# doodle_with_onboard_clock_smd_7805.net
KiCad netlist of a schematic drawn in EAGLE
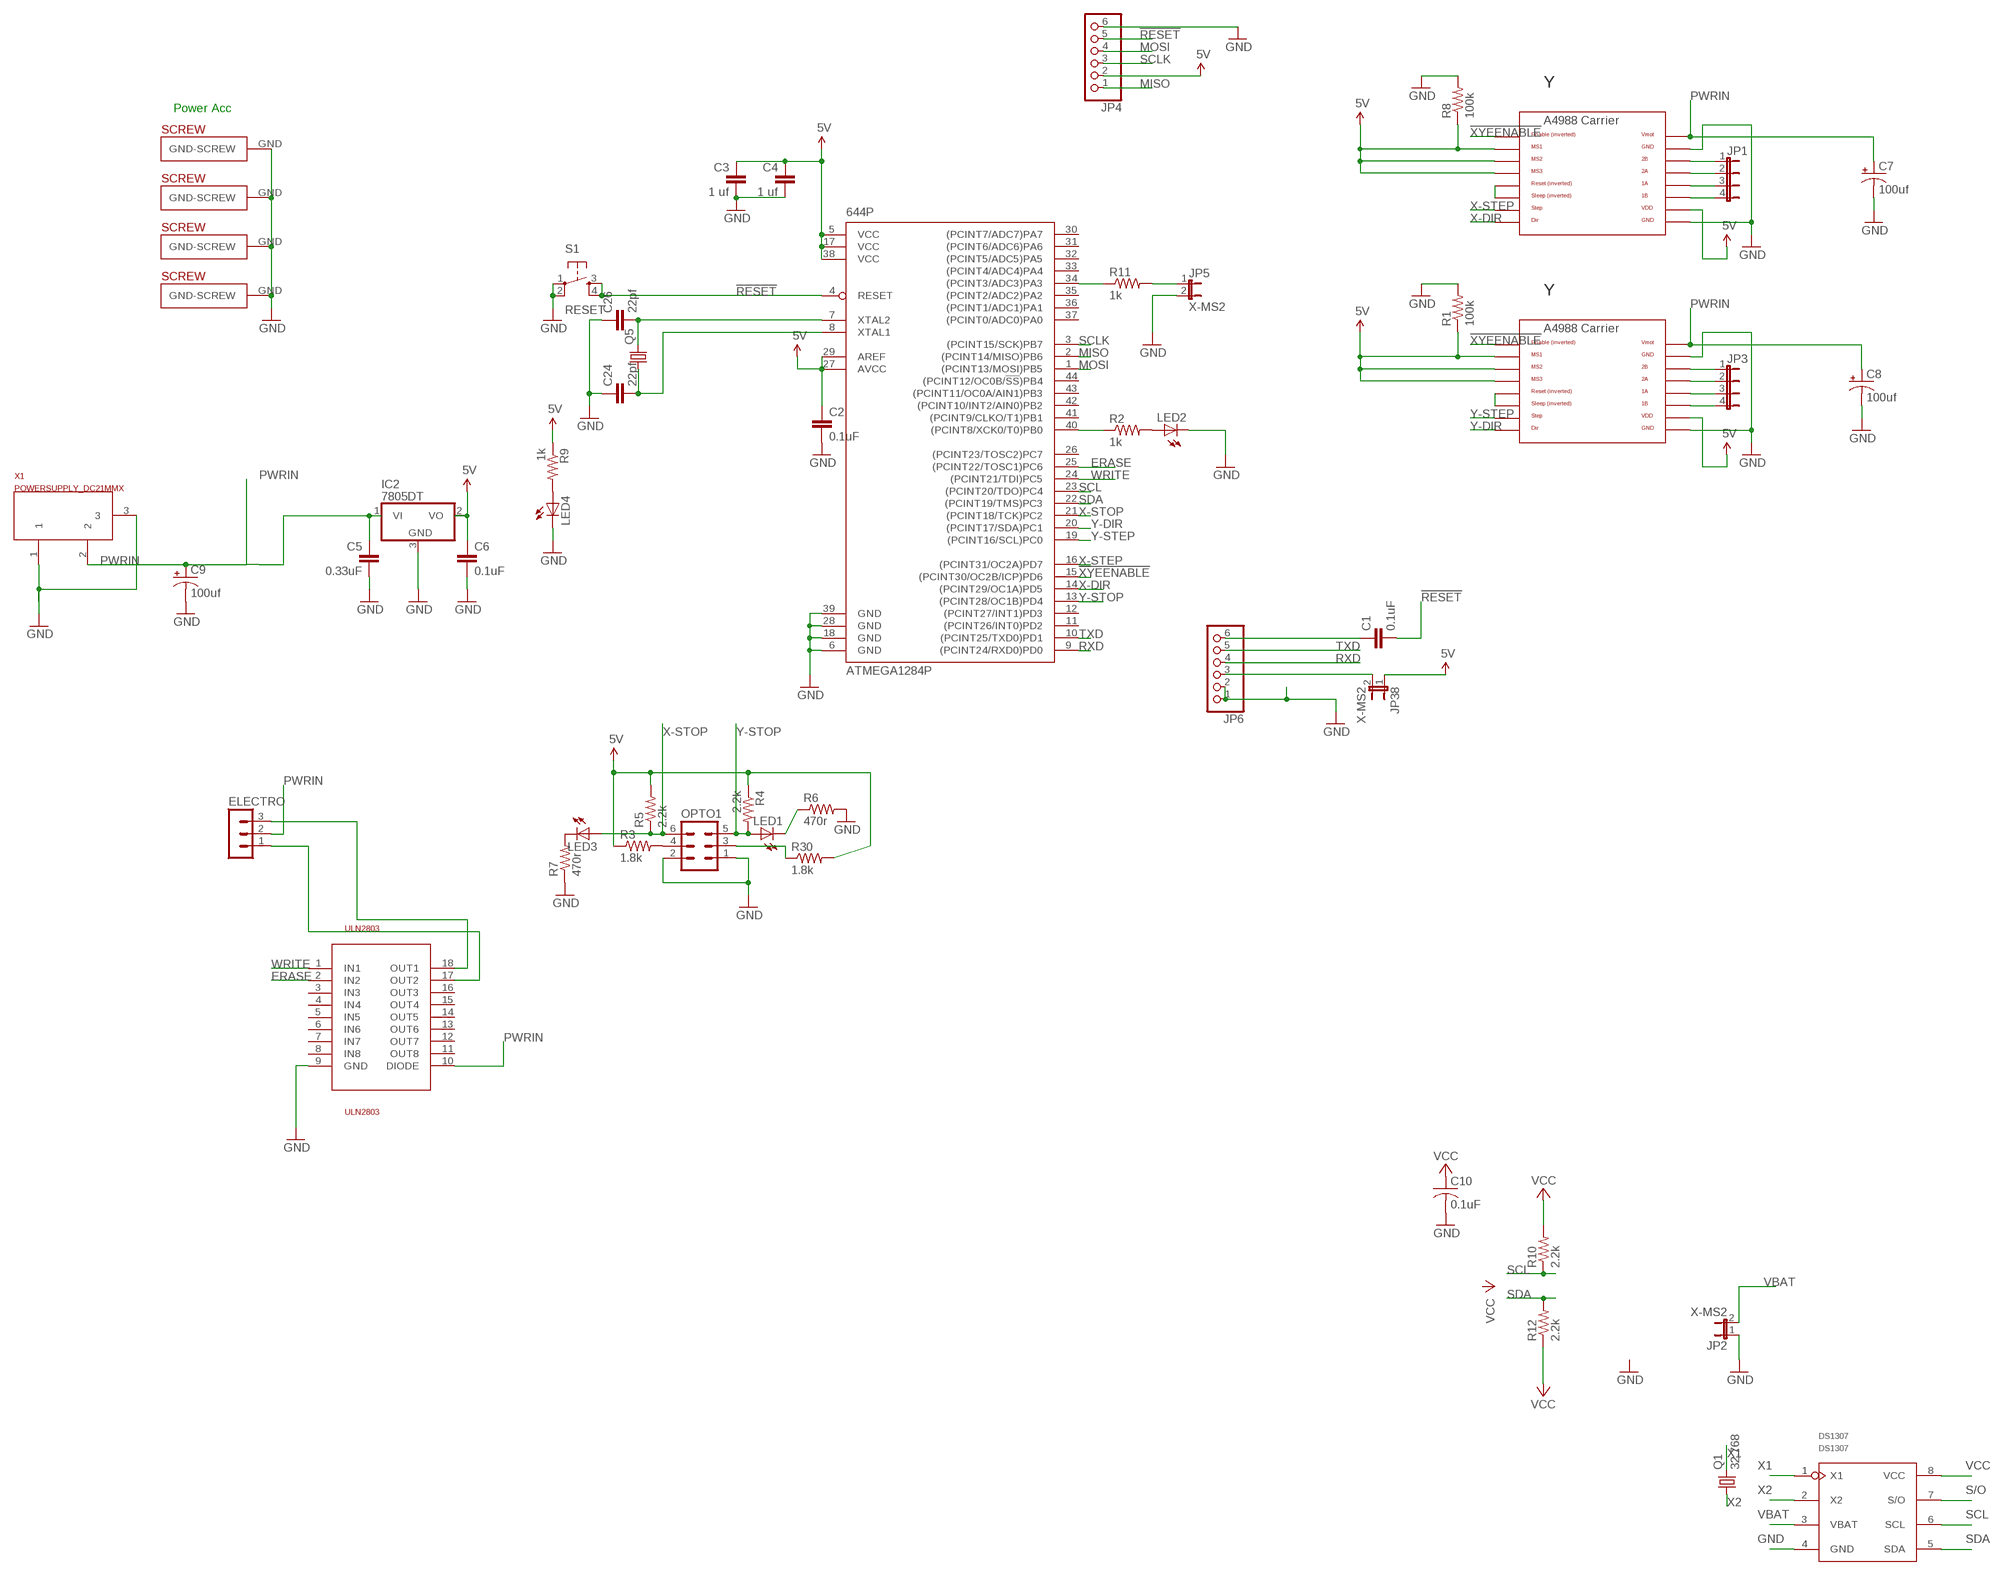
[diagram p0: schematic, sheet 1]

(export (version "E")
  (design (tool "Eeschema 10.0.6"))
  (components
    (comp (ref "644P")
      (value "ATMEGA1284P")
      (footprint "eagle-import:TQFP44")
      (fields (field (name "MPN") "ATMEGA644PV-10AU"))
      (libsource (lib "eagle-import") (part "ATMEGA644A"))
    )
    (comp (ref "C1")
      (value "0.1uF")
      (footprint "eagle-import:0805")
      (libsource (lib "eagle-import") (part "CAP0805"))
    )
    (comp (ref "C2")
      (value "0.1uF")
      (footprint "eagle-import:0805")
      (libsource (lib "eagle-import") (part "CAP0805"))
    )
    (comp (ref "C3")
      (value "1 uf")
      (footprint "eagle-import:0805")
      (libsource (lib "eagle-import") (part "CAP0805"))
    )
    (comp (ref "C4")
      (value "1 uf")
      (footprint "eagle-import:0805")
      (libsource (lib "eagle-import") (part "CAP0805"))
    )
    (comp (ref "C5")
      (value "0.33uF")
      (footprint "eagle-import:CAP-PTH-SMALL2")
      (libsource (lib "eagle-import") (part "CAPPTH2"))
    )
    (comp (ref "C6")
      (value "0.1uF")
      (footprint "eagle-import:CAP-PTH-SMALL2")
      (libsource (lib "eagle-import") (part "CAPPTH2"))
    )
    (comp (ref "C7")
      (value "100uf")
      (footprint "eagle-import:CPOL-RADIAL-100UF-25V")
      (libsource (lib "eagle-import") (part "CAP_POLPTH1"))
    )
    (comp (ref "C8")
      (value "100uf")
      (footprint "eagle-import:CPOL-RADIAL-100UF-25V")
      (libsource (lib "eagle-import") (part "CAP_POLPTH1"))
    )
    (comp (ref "C9")
      (value "100uf")
      (footprint "eagle-import:CPOL-RADIAL-100UF-25V")
      (libsource (lib "eagle-import") (part "CAP_POLPTH1"))
    )
    (comp (ref "C10")
      (value "0.1uF")
      (footprint "eagle-import:C0805")
      (libsource (lib "eagle-import") (part "C-USC0805"))
    )
    (comp (ref "C24")
      (value "22pf")
      (footprint "eagle-import:0805")
      (libsource (lib "eagle-import") (part "CAP0805"))
    )
    (comp (ref "C26")
      (value "22pf")
      (footprint "eagle-import:0805")
      (libsource (lib "eagle-import") (part "CAP0805"))
    )
    (comp (ref "DS1307")
      (value "DS1307")
      (footprint "eagle-import:SO08")
      (libsource (lib "eagle-import") (part "DS1307"))
    )
    (comp (ref "ELECTRO")
      (value "MA03-1")
      (footprint "eagle-import:MA03-1")
      (libsource (lib "eagle-import") (part "MA03-1"))
    )
    (comp (ref "IC2")
      (value "7805DT")
      (footprint "eagle-import:TO252")
      (libsource (lib "eagle-import") (part "78DT05"))
    )
    (comp (ref "JP1")
      (value "JP4E")
      (footprint "eagle-import:JP4")
      (libsource (lib "eagle-import") (part "JP4E"))
    )
    (comp (ref "JP2")
      (value "X-MS2")
      (footprint "eagle-import:1X02")
      (libsource (lib "eagle-import") (part "JUMPER-2PTH"))
    )
    (comp (ref "JP3")
      (value "JP4E")
      (footprint "eagle-import:JP4")
      (libsource (lib "eagle-import") (part "JP4E"))
    )
    (comp (ref "JP4")
      (value "PINHD-1X6/90")
      (footprint "eagle-import:1X06_90")
      (libsource (lib "eagle-import") (part "PINHD-1X6/90"))
    )
    (comp (ref "JP5")
      (value "X-MS2")
      (footprint "eagle-import:1X02")
      (libsource (lib "eagle-import") (part "JUMPER-2PTH"))
    )
    (comp (ref "JP6")
      (value "PINHD-1X6")
      (footprint "eagle-import:1X06")
      (libsource (lib "eagle-import") (part "PINHD-1X6"))
    )
    (comp (ref "JP38")
      (value "X-MS2")
      (footprint "eagle-import:1X02")
      (libsource (lib "eagle-import") (part "JUMPER-2PTH"))
    )
    (comp (ref "LED1")
      (value "LEDCHIPLED_0805")
      (footprint "eagle-import:CHIPLED_0805")
      (libsource (lib "eagle-import") (part "LEDCHIPLED_0805"))
    )
    (comp (ref "LED2")
      (value "LEDCHIPLED_0805")
      (footprint "eagle-import:CHIPLED_0805")
      (libsource (lib "eagle-import") (part "LEDCHIPLED_0805"))
    )
    (comp (ref "LED3")
      (value "LEDCHIPLED_0805")
      (footprint "eagle-import:CHIPLED_0805")
      (libsource (lib "eagle-import") (part "LEDCHIPLED_0805"))
    )
    (comp (ref "LED4")
      (value "LEDCHIPLED_0805")
      (footprint "eagle-import:CHIPLED_0805")
      (libsource (lib "eagle-import") (part "LEDCHIPLED_0805"))
    )
    (comp (ref "OPTO1")
      (value "MA03-2")
      (footprint "eagle-import:MA03-2")
      (libsource (lib "eagle-import") (part "MA03-2"))
    )
    (comp (ref "Q1")
      (value "32.768")
      (footprint "eagle-import:TC38H")
      (libsource (lib "eagle-import") (part "CRYTALTC38H"))
    )
    (comp (ref "Q5")
      (value "CRYSTALHC49S")
      (footprint "eagle-import:HC49_S")
      (libsource (lib "eagle-import") (part "CRYSTALHC49S"))
    )
    (comp (ref "R1")
      (value "100k")
      (footprint "eagle-import:0207_7")
      (libsource (lib "eagle-import") (part "R-US_0207/7"))
    )
    (comp (ref "R2")
      (value "1k")
      (footprint "eagle-import:R0805")
      (libsource (lib "eagle-import") (part "resistor_R-US_R0805"))
    )
    (comp (ref "R3")
      (value "1.8k")
      (footprint "eagle-import:R0805")
      (libsource (lib "eagle-import") (part "resistor_R-US_R0805"))
    )
    (comp (ref "R4")
      (value "2.2k")
      (footprint "eagle-import:R0805")
      (libsource (lib "eagle-import") (part "resistor_R-US_R0805"))
    )
    (comp (ref "R5")
      (value "2.2k")
      (footprint "eagle-import:R0805")
      (libsource (lib "eagle-import") (part "resistor_R-US_R0805"))
    )
    (comp (ref "R6")
      (value "470r")
      (footprint "eagle-import:R0805")
      (libsource (lib "eagle-import") (part "resistor_R-US_R0805"))
    )
    (comp (ref "R7")
      (value "470r")
      (footprint "eagle-import:R0805")
      (libsource (lib "eagle-import") (part "resistor_R-US_R0805"))
    )
    (comp (ref "R8")
      (value "100k")
      (footprint "eagle-import:0207_7")
      (libsource (lib "eagle-import") (part "R-US_0207/7"))
    )
    (comp (ref "R9")
      (value "1k")
      (footprint "eagle-import:R0805")
      (libsource (lib "eagle-import") (part "resistor_R-US_R0805"))
    )
    (comp (ref "R10")
      (value "2.2k")
      (footprint "eagle-import:R0805")
      (libsource (lib "eagle-import") (part "resistor_R-US_R0805"))
    )
    (comp (ref "R11")
      (value "1k")
      (footprint "eagle-import:R0805")
      (libsource (lib "eagle-import") (part "resistor_R-US_R0805"))
    )
    (comp (ref "R12")
      (value "2.2k")
      (footprint "eagle-import:R0805")
      (libsource (lib "eagle-import") (part "resistor_R-US_R0805"))
    )
    (comp (ref "R30")
      (value "1.8k")
      (footprint "eagle-import:R0603")
      (libsource (lib "eagle-import") (part "resistor_R-US_R0603"))
    )
    (comp (ref "S1")
      (value "RESET")
      (footprint "eagle-import:TACTILE-PTH")
      (libsource (lib "eagle-import") (part "TAC_SWITCHPTH"))
    )
    (comp (ref "U$1")
      (value "A4988BREAKOUT")
      (footprint "eagle-import:A4988BREAKOUT")
      (libsource (lib "eagle-import") (part "A4988BREAKOUT"))
    )
    (comp (ref "U$7")
      (value "A4988BREAKOUT")
      (footprint "eagle-import:A4988BREAKOUT")
      (libsource (lib "eagle-import") (part "A4988BREAKOUT"))
    )
    (comp (ref "U$14")
      (value "PLATED-SCREW")
      (footprint "eagle-import:PLATEDSCREW")
      (libsource (lib "eagle-import") (part "PLATED-SCREW"))
    )
    (comp (ref "U$17")
      (value "PLATED-SCREW")
      (footprint "eagle-import:PLATEDSCREW")
      (libsource (lib "eagle-import") (part "PLATED-SCREW"))
    )
    (comp (ref "U$18")
      (value "PLATED-SCREW")
      (footprint "eagle-import:PLATEDSCREW")
      (libsource (lib "eagle-import") (part "PLATED-SCREW"))
    )
    (comp (ref "U$38")
      (value "PLATED-SCREW")
      (footprint "eagle-import:PLATEDSCREW")
      (libsource (lib "eagle-import") (part "PLATED-SCREW"))
    )
    (comp (ref "ULN2803")
      (value "ULN2803")
      (footprint "eagle-import:SO18L")
      (libsource (lib "eagle-import") (part "ULN2803"))
    )
    (comp (ref "X1")
      (value "POWERSUPPLY_DC21MMX")
      (footprint "eagle-import:POWERSUPPLY_DC-21MM")
      (libsource (lib "eagle-import") (part "POWERSUPPLY_DC21MMX"))
    )
  )
  (nets
    (net (code "1") (name "/ERASE") (class "Default")
      (node (ref "644P") (pin "25") (pinfunction "(PCINT22/TOSC1)PC6_25") (pintype "output"))
      (node (ref "ULN2803") (pin "2") (pinfunction "IN2_2") (pintype "input"))
    )
    (net (code "2") (name "/MISO") (class "Default")
      (node (ref "644P") (pin "2") (pinfunction "(PCINT14/MISO)PB6_2") (pintype "bidirectional"))
      (node (ref "JP4") (pin "1") (pinfunction "1_1") (pintype "passive"))
    )
    (net (code "3") (name "/MOSI") (class "Default")
      (node (ref "644P") (pin "1") (pinfunction "(PCINT13/MOSI)PB5_1") (pintype "bidirectional"))
      (node (ref "JP4") (pin "4") (pinfunction "4_4") (pintype "passive"))
    )
    (net (code "4") (name "/PWRIN") (class "Default")
      (node (ref "C5") (pin "1") (pinfunction "1_1") (pintype "passive"))
      (node (ref "C7") (pin "1") (pinfunction "+_1") (pintype "passive"))
      (node (ref "C8") (pin "1") (pinfunction "+_1") (pintype "passive"))
      (node (ref "C9") (pin "1") (pinfunction "+_1") (pintype "passive"))
      (node (ref "ELECTRO") (pin "2") (pinfunction "2_2") (pintype "passive"))
      (node (ref "IC2") (pin "1") (pinfunction "VI_1") (pintype "input"))
      (node (ref "U$1") (pin "VMOT") (pinfunction "VMOT_VMOT") (pintype "power_in"))
      (node (ref "U$7") (pin "VMOT") (pinfunction "VMOT_VMOT") (pintype "power_in"))
      (node (ref "ULN2803") (pin "10") (pinfunction "DIODE_10") (pintype "power_in"))
      (node (ref "X1") (pin "2") (pinfunction "2_2") (pintype "power_in"))
    )
    (net (code "5") (name "/RXD") (class "Default")
      (node (ref "644P") (pin "9") (pinfunction "(PCINT24/RXD0)PD0_9") (pintype "bidirectional"))
      (node (ref "JP6") (pin "4") (pinfunction "4_4") (pintype "passive"))
    )
    (net (code "6") (name "/SCL") (class "Default")
      (node (ref "644P") (pin "23") (pinfunction "(PCINT20/TDO)PC4_23") (pintype "output"))
      (node (ref "DS1307") (pin "6") (pinfunction "SCL_6") (pintype "bidirectional"))
      (node (ref "R10") (pin "1") (pinfunction "1_1") (pintype "passive"))
    )
    (net (code "7") (name "/SCLK") (class "Default")
      (node (ref "644P") (pin "3") (pinfunction "(PCINT15/SCK)PB7_3") (pintype "bidirectional"))
      (node (ref "JP4") (pin "3") (pinfunction "3_3") (pintype "passive"))
    )
    (net (code "8") (name "/SDA") (class "Default")
      (node (ref "644P") (pin "22") (pinfunction "(PCINT19/TMS)PC3_22") (pintype "output"))
      (node (ref "DS1307") (pin "5") (pinfunction "SDA_5") (pintype "bidirectional"))
      (node (ref "R12") (pin "2") (pinfunction "2_2") (pintype "passive"))
    )
    (net (code "9") (name "/S{slash}O") (class "Default")
      (node (ref "DS1307") (pin "7") (pinfunction "S/O_7") (pintype "bidirectional"))
    )
    (net (code "10") (name "/TXD") (class "Default")
      (node (ref "644P") (pin "10") (pinfunction "(PCINT25/TXD0)PD1_10") (pintype "bidirectional"))
      (node (ref "JP6") (pin "5") (pinfunction "5_5") (pintype "passive"))
    )
    (net (code "11") (name "/VBAT") (class "Default")
      (node (ref "DS1307") (pin "3") (pinfunction "VBAT_3") (pintype "bidirectional"))
      (node (ref "JP2") (pin "2") (pinfunction "2_2") (pintype "passive"))
    )
    (net (code "12") (name "/WRITE") (class "Default")
      (node (ref "644P") (pin "24") (pinfunction "(PCINT21/TDI)PC5_24") (pintype "output"))
      (node (ref "ULN2803") (pin "1") (pinfunction "IN1_1") (pintype "input"))
    )
    (net (code "13") (name "/X-DIR") (class "Default")
      (node (ref "644P") (pin "14") (pinfunction "(PCINT29/OC1A)PD5_14") (pintype "bidirectional"))
      (node (ref "U$7") (pin "DIR") (pinfunction "DIR_DIR") (pintype "input"))
    )
    (net (code "14") (name "/X-STEP") (class "Default")
      (node (ref "644P") (pin "16") (pinfunction "(PCINT31/OC2A)PD7_16") (pintype "bidirectional"))
      (node (ref "U$7") (pin "STEP") (pinfunction "STEP_STEP") (pintype "input"))
    )
    (net (code "15") (name "/X-STOP") (class "Default")
      (node (ref "644P") (pin "21") (pinfunction "(PCINT18/TCK)PC2_21") (pintype "output"))
      (node (ref "LED3") (pin "A") (pinfunction "A_A") (pintype "passive"))
      (node (ref "OPTO1") (pin "6") (pinfunction "6_6") (pintype "passive"))
      (node (ref "R5") (pin "1") (pinfunction "1_1") (pintype "passive"))
    )
    (net (code "16") (name "/X1") (class "Default")
      (node (ref "DS1307") (pin "1") (pinfunction "X1_1") (pintype "bidirectional"))
      (node (ref "Q1") (pin "2") (pinfunction "2_2") (pintype "passive"))
    )
    (net (code "17") (name "/X2") (class "Default")
      (node (ref "DS1307") (pin "2") (pinfunction "X2_2") (pintype "bidirectional"))
      (node (ref "Q1") (pin "1") (pinfunction "1_1") (pintype "passive"))
    )
    (net (code "18") (name "/Y-DIR") (class "Default")
      (node (ref "644P") (pin "20") (pinfunction "(PCINT17/SDA)PC1_20") (pintype "output"))
      (node (ref "U$1") (pin "DIR") (pinfunction "DIR_DIR") (pintype "input"))
    )
    (net (code "19") (name "/Y-STEP") (class "Default")
      (node (ref "644P") (pin "19") (pinfunction "(PCINT16/SCL)PC0_19") (pintype "output"))
      (node (ref "U$1") (pin "STEP") (pinfunction "STEP_STEP") (pintype "input"))
    )
    (net (code "20") (name "/Y-STOP") (class "Default")
      (node (ref "644P") (pin "13") (pinfunction "(PCINT28/OC1B)PD4_13") (pintype "bidirectional"))
      (node (ref "LED1") (pin "A") (pinfunction "A_A") (pintype "passive"))
      (node (ref "OPTO1") (pin "5") (pinfunction "5_5") (pintype "passive"))
      (node (ref "R4") (pin "2") (pinfunction "2_2") (pintype "passive"))
    )
    (net (code "21") (name "/~{RESET}") (class "Default")
      (node (ref "644P") (pin "4") (pinfunction "RESET_4") (pintype "input"))
      (node (ref "C1") (pin "2") (pinfunction "2_2") (pintype "passive"))
      (node (ref "JP4") (pin "5") (pinfunction "5_5") (pintype "passive"))
      (node (ref "S1") (pin "3") (pinfunction "3_3") (pintype "passive"))
      (node (ref "S1") (pin "4") (pinfunction "4_4") (pintype "passive"))
    )
    (net (code "22") (name "/~{XYEENABLE}") (class "Default")
      (node (ref "644P") (pin "15") (pinfunction "(PCINT30/OC2B/ICP)PD6_15") (pintype "bidirectional"))
      (node (ref "U$1") (pin "EN") (pinfunction "EN_EN") (pintype "input"))
      (node (ref "U$7") (pin "EN") (pinfunction "EN_EN") (pintype "input"))
    )
    (net (code "23") (name "5V") (class "Default")
      (node (ref "644P") (pin "17") (pinfunction "VCC_17") (pintype "power_in"))
      (node (ref "644P") (pin "27") (pinfunction "AVCC_27") (pintype "power_in"))
      (node (ref "644P") (pin "29") (pinfunction "AREF_29") (pintype "passive"))
      (node (ref "644P") (pin "38") (pinfunction "VCC_38") (pintype "power_in"))
      (node (ref "644P") (pin "5") (pinfunction "VCC_5") (pintype "power_in"))
      (node (ref "C2") (pin "1") (pinfunction "1_1") (pintype "passive"))
      (node (ref "C3") (pin "1") (pinfunction "1_1") (pintype "passive"))
      (node (ref "C4") (pin "1") (pinfunction "1_1") (pintype "passive"))
      (node (ref "C6") (pin "1") (pinfunction "1_1") (pintype "passive"))
      (node (ref "IC2") (pin "2") (pinfunction "VO_2") (pintype "passive"))
      (node (ref "JP38") (pin "1") (pinfunction "1_1") (pintype "passive"))
      (node (ref "JP4") (pin "2") (pinfunction "2_2") (pintype "passive"))
      (node (ref "R1") (pin "1") (pinfunction "1_1") (pintype "passive"))
      (node (ref "R3") (pin "1") (pinfunction "1_1") (pintype "passive"))
      (node (ref "R30") (pin "2") (pinfunction "2_2") (pintype "passive"))
      (node (ref "R4") (pin "1") (pinfunction "1_1") (pintype "passive"))
      (node (ref "R5") (pin "2") (pinfunction "2_2") (pintype "passive"))
      (node (ref "R8") (pin "1") (pinfunction "1_1") (pintype "passive"))
      (node (ref "R9") (pin "1") (pinfunction "1_1") (pintype "passive"))
      (node (ref "U$1") (pin "MS1") (pinfunction "MS1_MS1") (pintype "input"))
      (node (ref "U$1") (pin "MS2") (pinfunction "MS2_MS2") (pintype "input"))
      (node (ref "U$1") (pin "MS3") (pinfunction "MS3_MS3") (pintype "input"))
      (node (ref "U$1") (pin "VDD") (pinfunction "VDD_VDD") (pintype "power_in"))
      (node (ref "U$7") (pin "MS1") (pinfunction "MS1_MS1") (pintype "input"))
      (node (ref "U$7") (pin "MS2") (pinfunction "MS2_MS2") (pintype "input"))
      (node (ref "U$7") (pin "MS3") (pinfunction "MS3_MS3") (pintype "input"))
      (node (ref "U$7") (pin "VDD") (pinfunction "VDD_VDD") (pintype "power_in"))
    )
    (net (code "24") (name "GND") (class "Default")
      (node (ref "644P") (pin "18") (pinfunction "GND_18") (pintype "power_in"))
      (node (ref "644P") (pin "28") (pinfunction "GND_28") (pintype "power_in"))
      (node (ref "644P") (pin "39") (pinfunction "GND_39") (pintype "power_in"))
      (node (ref "644P") (pin "6") (pinfunction "GND_6") (pintype "power_in"))
      (node (ref "C10") (pin "2") (pinfunction "2_2") (pintype "passive"))
      (node (ref "C2") (pin "2") (pinfunction "2_2") (pintype "passive"))
      (node (ref "C24") (pin "1") (pinfunction "1_1") (pintype "passive"))
      (node (ref "C26") (pin "1") (pinfunction "1_1") (pintype "passive"))
      (node (ref "C3") (pin "2") (pinfunction "2_2") (pintype "passive"))
      (node (ref "C4") (pin "2") (pinfunction "2_2") (pintype "passive"))
      (node (ref "C5") (pin "2") (pinfunction "2_2") (pintype "passive"))
      (node (ref "C6") (pin "2") (pinfunction "2_2") (pintype "passive"))
      (node (ref "C7") (pin "2") (pinfunction "-_2") (pintype "passive"))
      (node (ref "C8") (pin "2") (pinfunction "-_2") (pintype "passive"))
      (node (ref "C9") (pin "2") (pinfunction "-_2") (pintype "passive"))
      (node (ref "DS1307") (pin "4") (pinfunction "GND_4") (pintype "bidirectional"))
      (node (ref "IC2") (pin "3") (pinfunction "GND_3") (pintype "passive"))
      (node (ref "JP2") (pin "1") (pinfunction "1_1") (pintype "passive"))
      (node (ref "JP4") (pin "6") (pinfunction "6_6") (pintype "passive"))
      (node (ref "JP5") (pin "2") (pinfunction "2_2") (pintype "passive"))
      (node (ref "JP6") (pin "1") (pinfunction "1_1") (pintype "passive"))
      (node (ref "JP6") (pin "2") (pinfunction "2_2") (pintype "passive"))
      (node (ref "LED2") (pin "C") (pinfunction "C_C") (pintype "passive"))
      (node (ref "LED4") (pin "C") (pinfunction "C_C") (pintype "passive"))
      (node (ref "OPTO1") (pin "1") (pinfunction "1_1") (pintype "passive"))
      (node (ref "OPTO1") (pin "2") (pinfunction "2_2") (pintype "passive"))
      (node (ref "R1") (pin "2") (pinfunction "2_2") (pintype "passive"))
      (node (ref "R6") (pin "2") (pinfunction "2_2") (pintype "passive"))
      (node (ref "R7") (pin "1") (pinfunction "1_1") (pintype "passive"))
      (node (ref "R8") (pin "2") (pinfunction "2_2") (pintype "passive"))
      (node (ref "S1") (pin "1") (pinfunction "1_1") (pintype "passive"))
      (node (ref "S1") (pin "2") (pinfunction "2_2") (pintype "passive"))
      (node (ref "U$1") (pin "GND") (pinfunction "GND_GND") (pintype "power_in"))
      (node (ref "U$1") (pin "GND@0") (pinfunction "GND_GND@0") (pintype "power_in"))
      (node (ref "U$14") (pin "GND") (pinfunction "GND-SCREW_GND") (pintype "bidirectional"))
      (node (ref "U$17") (pin "GND") (pinfunction "GND-SCREW_GND") (pintype "bidirectional"))
      (node (ref "U$18") (pin "GND") (pinfunction "GND-SCREW_GND") (pintype "bidirectional"))
      (node (ref "U$38") (pin "GND") (pinfunction "GND-SCREW_GND") (pintype "bidirectional"))
      (node (ref "U$7") (pin "GND") (pinfunction "GND_GND") (pintype "power_in"))
      (node (ref "U$7") (pin "GND@0") (pinfunction "GND_GND@0") (pintype "power_in"))
      (node (ref "ULN2803") (pin "9") (pinfunction "GND_9") (pintype "power_in"))
      (node (ref "X1") (pin "1") (pinfunction "1_1") (pintype "power_in"))
      (node (ref "X1") (pin "3") (pinfunction "3_3") (pintype "power_in"))
    )
    (net (code "25") (name "Net-(644P-(PCINT3{slash}ADC3)PA3)") (class "Default")
      (node (ref "644P") (pin "34") (pinfunction "(PCINT3/ADC3)PA3_34") (pintype "bidirectional"))
      (node (ref "R11") (pin "1") (pinfunction "1_1") (pintype "passive"))
    )
    (net (code "26") (name "Net-(644P-(PCINT8{slash}XCK0{slash}T0)PB0)") (class "Default")
      (node (ref "644P") (pin "40") (pinfunction "(PCINT8/XCK0/T0)PB0_40") (pintype "bidirectional"))
      (node (ref "R2") (pin "1") (pinfunction "1_1") (pintype "passive"))
    )
    (net (code "27") (name "Net-(644P-XTAL1)") (class "Default")
      (node (ref "644P") (pin "8") (pinfunction "XTAL1_8") (pintype "bidirectional"))
      (node (ref "C24") (pin "2") (pinfunction "2_2") (pintype "passive"))
      (node (ref "Q5") (pin "1") (pinfunction "1_1") (pintype "passive"))
    )
    (net (code "28") (name "Net-(644P-XTAL2)") (class "Default")
      (node (ref "644P") (pin "7") (pinfunction "XTAL2_7") (pintype "bidirectional"))
      (node (ref "C26") (pin "2") (pinfunction "2_2") (pintype "passive"))
      (node (ref "Q5") (pin "2") (pinfunction "2_2") (pintype "passive"))
    )
    (net (code "29") (name "Net-(C1-Pad1)") (class "Default")
      (node (ref "C1") (pin "1") (pinfunction "1_1") (pintype "passive"))
      (node (ref "JP6") (pin "6") (pinfunction "6_6") (pintype "passive"))
    )
    (net (code "30") (name "Net-(JP1-Pad1)") (class "Default")
      (node (ref "JP1") (pin "1") (pinfunction "1_1") (pintype "passive"))
      (node (ref "U$7") (pin "2B") (pinfunction "2B_2B") (pintype "output"))
    )
    (net (code "31") (name "Net-(JP1-Pad2)") (class "Default")
      (node (ref "JP1") (pin "2") (pinfunction "2_2") (pintype "passive"))
      (node (ref "U$7") (pin "2A") (pinfunction "2A_2A") (pintype "output"))
    )
    (net (code "32") (name "Net-(JP1-Pad3)") (class "Default")
      (node (ref "JP1") (pin "3") (pinfunction "3_3") (pintype "passive"))
      (node (ref "U$7") (pin "1A") (pinfunction "1A_1A") (pintype "output"))
    )
    (net (code "33") (name "Net-(JP1-Pad4)") (class "Default")
      (node (ref "JP1") (pin "4") (pinfunction "4_4") (pintype "passive"))
      (node (ref "U$7") (pin "1B") (pinfunction "1B_1B") (pintype "output"))
    )
    (net (code "34") (name "Net-(JP3-Pad1)") (class "Default")
      (node (ref "JP3") (pin "1") (pinfunction "1_1") (pintype "passive"))
      (node (ref "U$1") (pin "2B") (pinfunction "2B_2B") (pintype "output"))
    )
    (net (code "35") (name "Net-(JP3-Pad2)") (class "Default")
      (node (ref "JP3") (pin "2") (pinfunction "2_2") (pintype "passive"))
      (node (ref "U$1") (pin "2A") (pinfunction "2A_2A") (pintype "output"))
    )
    (net (code "36") (name "Net-(JP3-Pad3)") (class "Default")
      (node (ref "JP3") (pin "3") (pinfunction "3_3") (pintype "passive"))
      (node (ref "U$1") (pin "1A") (pinfunction "1A_1A") (pintype "output"))
    )
    (net (code "37") (name "Net-(JP3-Pad4)") (class "Default")
      (node (ref "JP3") (pin "4") (pinfunction "4_4") (pintype "passive"))
      (node (ref "U$1") (pin "1B") (pinfunction "1B_1B") (pintype "output"))
    )
    (net (code "38") (name "Net-(JP5-Pad1)") (class "Default")
      (node (ref "JP5") (pin "1") (pinfunction "1_1") (pintype "passive"))
      (node (ref "R11") (pin "2") (pinfunction "2_2") (pintype "passive"))
    )
    (net (code "39") (name "Net-(JP38-Pad2)") (class "Default")
      (node (ref "JP38") (pin "2") (pinfunction "2_2") (pintype "passive"))
      (node (ref "JP6") (pin "3") (pinfunction "3_3") (pintype "passive"))
    )
    (net (code "40") (name "Net-(LED1-PadC)") (class "Default")
      (node (ref "LED1") (pin "C") (pinfunction "C_C") (pintype "passive"))
      (node (ref "R6") (pin "1") (pinfunction "1_1") (pintype "passive"))
    )
    (net (code "41") (name "Net-(LED2-PadA)") (class "Default")
      (node (ref "LED2") (pin "A") (pinfunction "A_A") (pintype "passive"))
      (node (ref "R2") (pin "2") (pinfunction "2_2") (pintype "passive"))
    )
    (net (code "42") (name "Net-(LED3-PadC)") (class "Default")
      (node (ref "LED3") (pin "C") (pinfunction "C_C") (pintype "passive"))
      (node (ref "R7") (pin "2") (pinfunction "2_2") (pintype "passive"))
    )
    (net (code "43") (name "Net-(LED4-PadA)") (class "Default")
      (node (ref "LED4") (pin "A") (pinfunction "A_A") (pintype "passive"))
      (node (ref "R9") (pin "2") (pinfunction "2_2") (pintype "passive"))
    )
    (net (code "44") (name "Net-(OPTO1-Pad3)") (class "Default")
      (node (ref "OPTO1") (pin "3") (pinfunction "3_3") (pintype "passive"))
      (node (ref "R30") (pin "1") (pinfunction "1_1") (pintype "passive"))
    )
    (net (code "45") (name "Net-(OPTO1-Pad4)") (class "Default")
      (node (ref "OPTO1") (pin "4") (pinfunction "4_4") (pintype "passive"))
      (node (ref "R3") (pin "2") (pinfunction "2_2") (pintype "passive"))
    )
    (net (code "46") (name "Net-(U$1-SLEEP)") (class "Default")
      (node (ref "U$1") (pin "RST") (pinfunction "RST_RST") (pintype "input"))
      (node (ref "U$1") (pin "SLP") (pinfunction "SLEEP_SLP") (pintype "input"))
    )
    (net (code "47") (name "Net-(U$7-SLEEP)") (class "Default")
      (node (ref "U$7") (pin "RST") (pinfunction "RST_RST") (pintype "input"))
      (node (ref "U$7") (pin "SLP") (pinfunction "SLEEP_SLP") (pintype "input"))
    )
    (net (code "48") (name "Net-(ULN2803-OUT1)") (class "Default")
      (node (ref "ELECTRO") (pin "3") (pinfunction "3_3") (pintype "passive"))
      (node (ref "ULN2803") (pin "18") (pinfunction "OUT1_18") (pintype "open_collector"))
    )
    (net (code "49") (name "Net-(ULN2803-OUT2)") (class "Default")
      (node (ref "ELECTRO") (pin "1") (pinfunction "1_1") (pintype "passive"))
      (node (ref "ULN2803") (pin "17") (pinfunction "OUT2_17") (pintype "open_collector"))
    )
    (net (code "50") (name "VCC") (class "Default")
      (node (ref "C10") (pin "1") (pinfunction "1_1") (pintype "passive"))
      (node (ref "DS1307") (pin "8") (pinfunction "VCC_8") (pintype "bidirectional"))
      (node (ref "R10") (pin "2") (pinfunction "2_2") (pintype "passive"))
      (node (ref "R12") (pin "1") (pinfunction "1_1") (pintype "passive"))
    )
    (net (code "51") (name "unconnected-(644P-(PCINT0{slash}ADC0)PA0-Pad37)") (class "Default")
      (node (ref "644P") (pin "37") (pinfunction "(PCINT0/ADC0)PA0_37") (pintype "bidirectional"))
    )
    (net (code "52") (name "unconnected-(644P-(PCINT1{slash}ADC1)PA1-Pad36)") (class "Default")
      (node (ref "644P") (pin "36") (pinfunction "(PCINT1/ADC1)PA1_36") (pintype "bidirectional"))
    )
    (net (code "53") (name "unconnected-(644P-(PCINT2{slash}ADC2)PA2-Pad35)") (class "Default")
      (node (ref "644P") (pin "35") (pinfunction "(PCINT2/ADC2)PA2_35") (pintype "bidirectional"))
    )
    (net (code "54") (name "unconnected-(644P-(PCINT4{slash}ADC4)PA4-Pad33)") (class "Default")
      (node (ref "644P") (pin "33") (pinfunction "(PCINT4/ADC4)PA4_33") (pintype "bidirectional"))
    )
    (net (code "55") (name "unconnected-(644P-(PCINT5{slash}ADC5)PA5-Pad32)") (class "Default")
      (node (ref "644P") (pin "32") (pinfunction "(PCINT5/ADC5)PA5_32") (pintype "bidirectional"))
    )
    (net (code "56") (name "unconnected-(644P-(PCINT6{slash}ADC6)PA6-Pad31)") (class "Default")
      (node (ref "644P") (pin "31") (pinfunction "(PCINT6/ADC6)PA6_31") (pintype "bidirectional"))
    )
    (net (code "57") (name "unconnected-(644P-(PCINT7{slash}ADC7)PA7-Pad30)") (class "Default")
      (node (ref "644P") (pin "30") (pinfunction "(PCINT7/ADC7)PA7_30") (pintype "bidirectional"))
    )
    (net (code "58") (name "unconnected-(644P-(PCINT9{slash}CLKO{slash}T1)PB1-Pad41)") (class "Default")
      (node (ref "644P") (pin "41") (pinfunction "(PCINT9/CLKO/T1)PB1_41") (pintype "bidirectional"))
    )
    (net (code "59") (name "unconnected-(644P-(PCINT10{slash}INT2{slash}AIN0)PB2-Pad42)") (class "Default")
      (node (ref "644P") (pin "42") (pinfunction "(PCINT10/INT2/AIN0)PB2_42") (pintype "bidirectional"))
    )
    (net (code "60") (name "unconnected-(644P-(PCINT11{slash}OC0A{slash}AIN1)PB3-Pad43)") (class "Default")
      (node (ref "644P") (pin "43") (pinfunction "(PCINT11/OC0A/AIN1)PB3_43") (pintype "bidirectional"))
    )
    (net (code "61") (name "unconnected-(644P-(PCINT12{slash}OC0B{slash}~{SS})PB4-Pad44)") (class "Default")
      (node (ref "644P") (pin "44") (pinfunction "(PCINT12/OC0B/~{SS})PB4_44") (pintype "bidirectional"))
    )
    (net (code "62") (name "unconnected-(644P-(PCINT23{slash}TOSC2)PC7-Pad26)") (class "Default")
      (node (ref "644P") (pin "26") (pinfunction "(PCINT23/TOSC2)PC7_26") (pintype "output"))
    )
    (net (code "63") (name "unconnected-(644P-(PCINT26{slash}INT0)PD2-Pad11)") (class "Default")
      (node (ref "644P") (pin "11") (pinfunction "(PCINT26/INT0)PD2_11") (pintype "bidirectional"))
    )
    (net (code "64") (name "unconnected-(644P-(PCINT27{slash}INT1)PD3-Pad12)") (class "Default")
      (node (ref "644P") (pin "12") (pinfunction "(PCINT27/INT1)PD3_12") (pintype "bidirectional"))
    )
    (net (code "65") (name "unconnected-(ULN2803-IN3-Pad3)") (class "Default")
      (node (ref "ULN2803") (pin "3") (pinfunction "IN3_3") (pintype "input"))
    )
    (net (code "66") (name "unconnected-(ULN2803-IN4-Pad4)") (class "Default")
      (node (ref "ULN2803") (pin "4") (pinfunction "IN4_4") (pintype "input"))
    )
    (net (code "67") (name "unconnected-(ULN2803-IN5-Pad5)") (class "Default")
      (node (ref "ULN2803") (pin "5") (pinfunction "IN5_5") (pintype "input"))
    )
    (net (code "68") (name "unconnected-(ULN2803-IN6-Pad6)") (class "Default")
      (node (ref "ULN2803") (pin "6") (pinfunction "IN6_6") (pintype "input"))
    )
    (net (code "69") (name "unconnected-(ULN2803-IN7-Pad7)") (class "Default")
      (node (ref "ULN2803") (pin "7") (pinfunction "IN7_7") (pintype "input"))
    )
    (net (code "70") (name "unconnected-(ULN2803-IN8-Pad8)") (class "Default")
      (node (ref "ULN2803") (pin "8") (pinfunction "IN8_8") (pintype "input"))
    )
    (net (code "71") (name "unconnected-(ULN2803-OUT3-Pad16)") (class "Default")
      (node (ref "ULN2803") (pin "16") (pinfunction "OUT3_16") (pintype "open_collector"))
    )
    (net (code "72") (name "unconnected-(ULN2803-OUT4-Pad15)") (class "Default")
      (node (ref "ULN2803") (pin "15") (pinfunction "OUT4_15") (pintype "open_collector"))
    )
    (net (code "73") (name "unconnected-(ULN2803-OUT5-Pad14)") (class "Default")
      (node (ref "ULN2803") (pin "14") (pinfunction "OUT5_14") (pintype "open_collector"))
    )
    (net (code "74") (name "unconnected-(ULN2803-OUT6-Pad13)") (class "Default")
      (node (ref "ULN2803") (pin "13") (pinfunction "OUT6_13") (pintype "open_collector"))
    )
    (net (code "75") (name "unconnected-(ULN2803-OUT7-Pad12)") (class "Default")
      (node (ref "ULN2803") (pin "12") (pinfunction "OUT7_12") (pintype "open_collector"))
    )
    (net (code "76") (name "unconnected-(ULN2803-OUT8-Pad11)") (class "Default")
      (node (ref "ULN2803") (pin "11") (pinfunction "OUT8_11") (pintype "open_collector"))
    )
  )
)
